# display_buttons.net
KiCad netlist of a schematic drawn in EAGLE
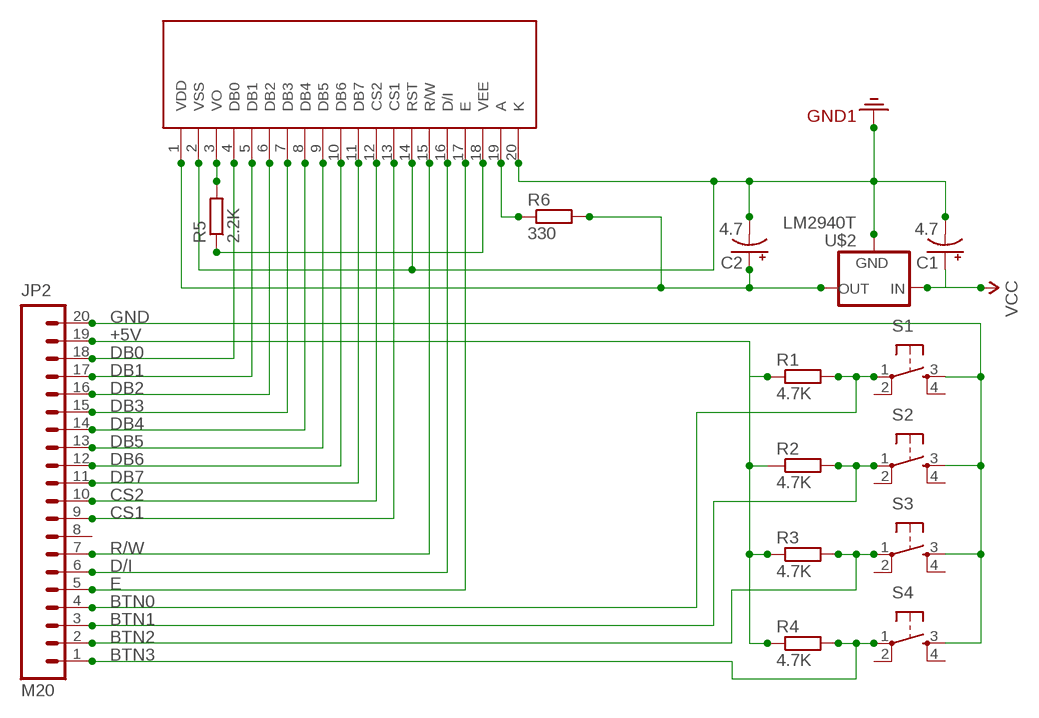
[diagram p0: schematic, sheet 1]

(export (version "E")
  (design (tool "Eeschema 10.0.6"))
  (components
    (comp (ref "C1")
      (value "4.7")
      (footprint "eagle-import:CPOL-RADIAL-10UF-25V")
      (libsource (lib "eagle-import") (part "CAP_POLPTH2"))
    )
    (comp (ref "C2")
      (value "4.7")
      (footprint "eagle-import:CPOL-RADIAL-10UF-25V")
      (libsource (lib "eagle-import") (part "CAP_POLPTH2"))
    )
    (comp (ref "JP2")
      (value "M20")
      (footprint "eagle-import:1X20")
      (libsource (lib "eagle-import") (part "M20"))
    )
    (comp (ref "R1")
      (value "4.7K")
      (footprint "eagle-import:0204_7")
      (libsource (lib "eagle-import") (part "R-EU_0204/7"))
    )
    (comp (ref "R2")
      (value "4.7K")
      (footprint "eagle-import:0204_7")
      (libsource (lib "eagle-import") (part "R-EU_0204/7"))
    )
    (comp (ref "R3")
      (value "4.7K")
      (footprint "eagle-import:0204_7")
      (libsource (lib "eagle-import") (part "R-EU_0204/7"))
    )
    (comp (ref "R4")
      (value "4.7K")
      (footprint "eagle-import:0204_7")
      (libsource (lib "eagle-import") (part "R-EU_0204/7"))
    )
    (comp (ref "R5")
      (value "2.2K")
      (footprint "eagle-import:0204_7")
      (libsource (lib "eagle-import") (part "R-EU_0204/7"))
    )
    (comp (ref "R6")
      (value "330")
      (footprint "eagle-import:0204_7")
      (libsource (lib "eagle-import") (part "R-EU_0204/7"))
    )
    (comp (ref "S1")
      (value "TAC_SWITCHPTH")
      (footprint "eagle-import:TACTILE-PTH")
      (libsource (lib "eagle-import") (part "TAC_SWITCHPTH"))
    )
    (comp (ref "S2")
      (value "TAC_SWITCHPTH")
      (footprint "eagle-import:TACTILE-PTH")
      (libsource (lib "eagle-import") (part "TAC_SWITCHPTH"))
    )
    (comp (ref "S3")
      (value "TAC_SWITCHPTH")
      (footprint "eagle-import:TACTILE-PTH")
      (libsource (lib "eagle-import") (part "TAC_SWITCHPTH"))
    )
    (comp (ref "S4")
      (value "TAC_SWITCHPTH")
      (footprint "eagle-import:TACTILE-PTH")
      (libsource (lib "eagle-import") (part "TAC_SWITCHPTH"))
    )
    (comp (ref "U$1")
      (value "LCD-G12864FULL")
      (footprint "eagle-import:LCD-G12864")
      (libsource (lib "eagle-import") (part "LCD-G12864FULL"))
    )
    (comp (ref "U$2")
      (value "LM2940T")
      (footprint "eagle-import:78XXL")
      (libsource (lib "eagle-import") (part "V_REG_LD1117VXX"))
    )
  )
  (nets
    (net (code "1") (name "/+5V") (class "Default")
      (node (ref "JP2") (pin "19") (pinfunction "19_19") (pintype "passive"))
      (node (ref "R1") (pin "1") (pinfunction "1_1") (pintype "passive"))
      (node (ref "R2") (pin "1") (pinfunction "1_1") (pintype "passive"))
      (node (ref "R3") (pin "1") (pinfunction "1_1") (pintype "passive"))
      (node (ref "R4") (pin "1") (pinfunction "1_1") (pintype "passive"))
    )
    (net (code "2") (name "/BTN0") (class "Default")
      (node (ref "JP2") (pin "4") (pinfunction "4_4") (pintype "passive"))
      (node (ref "R1") (pin "2") (pinfunction "2_2") (pintype "passive"))
      (node (ref "S1") (pin "1") (pinfunction "1_1") (pintype "passive"))
    )
    (net (code "3") (name "/BTN1") (class "Default")
      (node (ref "JP2") (pin "3") (pinfunction "3_3") (pintype "passive"))
      (node (ref "R2") (pin "2") (pinfunction "2_2") (pintype "passive"))
      (node (ref "S2") (pin "1") (pinfunction "1_1") (pintype "passive"))
    )
    (net (code "4") (name "/BTN2") (class "Default")
      (node (ref "JP2") (pin "2") (pinfunction "2_2") (pintype "passive"))
      (node (ref "R3") (pin "2") (pinfunction "2_2") (pintype "passive"))
      (node (ref "S3") (pin "1") (pinfunction "1_1") (pintype "passive"))
    )
    (net (code "5") (name "/BTN3") (class "Default")
      (node (ref "JP2") (pin "1") (pinfunction "1_1") (pintype "passive"))
      (node (ref "R4") (pin "2") (pinfunction "2_2") (pintype "passive"))
      (node (ref "S4") (pin "1") (pinfunction "1_1") (pintype "passive"))
    )
    (net (code "6") (name "/CS1") (class "Default")
      (node (ref "JP2") (pin "9") (pinfunction "9_9") (pintype "passive"))
      (node (ref "U$1") (pin "13") (pinfunction "CS1_13") (pintype "input"))
    )
    (net (code "7") (name "/CS2") (class "Default")
      (node (ref "JP2") (pin "10") (pinfunction "10_10") (pintype "passive"))
      (node (ref "U$1") (pin "12") (pinfunction "CS2_12") (pintype "input"))
    )
    (net (code "8") (name "/DB0") (class "Default")
      (node (ref "JP2") (pin "18") (pinfunction "18_18") (pintype "passive"))
      (node (ref "U$1") (pin "4") (pinfunction "DB0_4") (pintype "bidirectional"))
    )
    (net (code "9") (name "/DB1") (class "Default")
      (node (ref "JP2") (pin "17") (pinfunction "17_17") (pintype "passive"))
      (node (ref "U$1") (pin "5") (pinfunction "DB1_5") (pintype "bidirectional"))
    )
    (net (code "10") (name "/DB2") (class "Default")
      (node (ref "JP2") (pin "16") (pinfunction "16_16") (pintype "passive"))
      (node (ref "U$1") (pin "6") (pinfunction "DB2_6") (pintype "bidirectional"))
    )
    (net (code "11") (name "/DB3") (class "Default")
      (node (ref "JP2") (pin "15") (pinfunction "15_15") (pintype "passive"))
      (node (ref "U$1") (pin "7") (pinfunction "DB3_7") (pintype "bidirectional"))
    )
    (net (code "12") (name "/DB4") (class "Default")
      (node (ref "JP2") (pin "14") (pinfunction "14_14") (pintype "passive"))
      (node (ref "U$1") (pin "8") (pinfunction "DB4_8") (pintype "bidirectional"))
    )
    (net (code "13") (name "/DB5") (class "Default")
      (node (ref "JP2") (pin "13") (pinfunction "13_13") (pintype "passive"))
      (node (ref "U$1") (pin "9") (pinfunction "DB5_9") (pintype "bidirectional"))
    )
    (net (code "14") (name "/DB6") (class "Default")
      (node (ref "JP2") (pin "12") (pinfunction "12_12") (pintype "passive"))
      (node (ref "U$1") (pin "10") (pinfunction "DB6_10") (pintype "bidirectional"))
    )
    (net (code "15") (name "/DB7") (class "Default")
      (node (ref "JP2") (pin "11") (pinfunction "11_11") (pintype "passive"))
      (node (ref "U$1") (pin "11") (pinfunction "DB7_11") (pintype "bidirectional"))
    )
    (net (code "16") (name "/D{slash}I") (class "Default")
      (node (ref "JP2") (pin "6") (pinfunction "6_6") (pintype "passive"))
      (node (ref "U$1") (pin "16") (pinfunction "D/I_16") (pintype "input"))
    )
    (net (code "17") (name "/E") (class "Default")
      (node (ref "JP2") (pin "5") (pinfunction "5_5") (pintype "passive"))
      (node (ref "U$1") (pin "17") (pinfunction "E_17") (pintype "input"))
    )
    (net (code "18") (name "/GND") (class "Default")
      (node (ref "JP2") (pin "20") (pinfunction "20_20") (pintype "passive"))
      (node (ref "S1") (pin "3") (pinfunction "3_3") (pintype "passive"))
      (node (ref "S2") (pin "3") (pinfunction "3_3") (pintype "passive"))
      (node (ref "S3") (pin "3") (pinfunction "3_3") (pintype "passive"))
      (node (ref "S4") (pin "3") (pinfunction "3_3") (pintype "passive"))
    )
    (net (code "19") (name "/R{slash}W") (class "Default")
      (node (ref "JP2") (pin "7") (pinfunction "7_7") (pintype "passive"))
      (node (ref "U$1") (pin "15") (pinfunction "R/W_15") (pintype "input"))
    )
    (net (code "20") (name "GND2") (class "Default")
      (node (ref "C1") (pin "2") (pinfunction "-_2") (pintype "passive"))
      (node (ref "C2") (pin "2") (pinfunction "-_2") (pintype "passive"))
      (node (ref "U$1") (pin "14") (pinfunction "RST_14") (pintype "input"))
      (node (ref "U$1") (pin "2") (pinfunction "VSS_2") (pintype "power_in"))
      (node (ref "U$1") (pin "20") (pinfunction "K_20") (pintype "power_in"))
      (node (ref "U$2") (pin "IN") (pinfunction "GND_IN") (pintype "input"))
    )
    (net (code "21") (name "Net-(C2-+)") (class "Default")
      (node (ref "C2") (pin "1") (pinfunction "+_1") (pintype "passive"))
      (node (ref "R6") (pin "2") (pinfunction "2_2") (pintype "passive"))
      (node (ref "U$1") (pin "1") (pinfunction "VDD_1") (pintype "power_in"))
      (node (ref "U$2") (pin "GND") (pinfunction "OUT_GND") (pintype "output"))
    )
    (net (code "22") (name "Net-(U$1-A)") (class "Default")
      (node (ref "R6") (pin "1") (pinfunction "1_1") (pintype "passive"))
      (node (ref "U$1") (pin "19") (pinfunction "A_19") (pintype "power_in"))
    )
    (net (code "23") (name "Net-(U$1-VEE)") (class "Default")
      (node (ref "R5") (pin "1") (pinfunction "1_1") (pintype "passive"))
      (node (ref "U$1") (pin "18") (pinfunction "VEE_18") (pintype "bidirectional"))
    )
    (net (code "24") (name "Net-(U$1-VO)") (class "Default")
      (node (ref "R5") (pin "2") (pinfunction "2_2") (pintype "passive"))
      (node (ref "U$1") (pin "3") (pinfunction "VO_3") (pintype "bidirectional"))
    )
    (net (code "25") (name "VCC") (class "Default")
      (node (ref "C1") (pin "1") (pinfunction "+_1") (pintype "passive"))
      (node (ref "U$2") (pin "OUT") (pinfunction "IN_OUT") (pintype "input"))
    )
    (net (code "26") (name "unconnected-(JP2-Pad8)") (class "Default")
      (node (ref "JP2") (pin "8") (pinfunction "8_8") (pintype "passive"))
    )
    (net (code "27") (name "unconnected-(S1-Pad2)") (class "Default")
      (node (ref "S1") (pin "2") (pinfunction "2_2") (pintype "passive"))
    )
    (net (code "28") (name "unconnected-(S1-Pad4)") (class "Default")
      (node (ref "S1") (pin "4") (pinfunction "4_4") (pintype "passive"))
    )
    (net (code "29") (name "unconnected-(S2-Pad2)") (class "Default")
      (node (ref "S2") (pin "2") (pinfunction "2_2") (pintype "passive"))
    )
    (net (code "30") (name "unconnected-(S2-Pad4)") (class "Default")
      (node (ref "S2") (pin "4") (pinfunction "4_4") (pintype "passive"))
    )
    (net (code "31") (name "unconnected-(S3-Pad2)") (class "Default")
      (node (ref "S3") (pin "2") (pinfunction "2_2") (pintype "passive"))
    )
    (net (code "32") (name "unconnected-(S3-Pad4)") (class "Default")
      (node (ref "S3") (pin "4") (pinfunction "4_4") (pintype "passive"))
    )
    (net (code "33") (name "unconnected-(S4-Pad2)") (class "Default")
      (node (ref "S4") (pin "2") (pinfunction "2_2") (pintype "passive"))
    )
    (net (code "34") (name "unconnected-(S4-Pad4)") (class "Default")
      (node (ref "S4") (pin "4") (pinfunction "4_4") (pintype "passive"))
    )
  )
)
